# Mechanical.net
KiCad netlist of a schematic drawn in Altium Designer
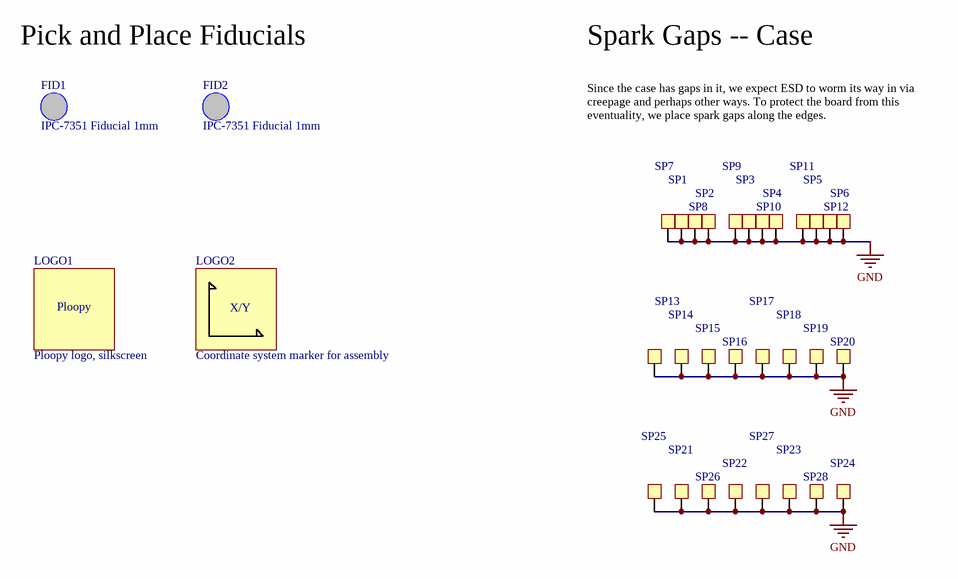
[diagram p0: Mechanical.SchDoc]

(export (version "E")
  (design (tool "Eeschema 10.0.6"))
  (components
    (comp (ref "FID1")
      (value "IPC-7351 Fiducial 1mm")
      (footprint "FIDUCIAL_1.5")
      (libsource (lib "Mechanical") (part "FIDUCIAL_1.5"))
    )
    (comp (ref "FID2")
      (value "IPC-7351 Fiducial 1mm")
      (footprint "FIDUCIAL_1.5")
      (libsource (lib "Mechanical") (part "FIDUCIAL_1.5"))
    )
    (comp (ref "LOGO1")
      (value "Ploopy logo, silkscreen")
      (footprint "PloopyLogo")
      (libsource (lib "Graphics") (part "PloopyLogo"))
    )
    (comp (ref "LOGO2")
      (value "Coordinate system marker for assembly")
      (footprint "Coordinate System")
      (libsource (lib "Graphics") (part "CoordinateSystem"))
    )
    (comp (ref "SP1")
      (value "Spark Gap")
      (footprint "SparkGap")
      (description "Open square pad for spark gapping")
      (libsource (lib "PCBFeatures") (part "Spark Gap"))
    )
    (comp (ref "SP2")
      (value "Spark Gap")
      (footprint "SparkGap")
      (description "Open square pad for spark gapping")
      (libsource (lib "PCBFeatures") (part "Spark Gap"))
    )
    (comp (ref "SP3")
      (value "Spark Gap")
      (footprint "SparkGap")
      (description "Open square pad for spark gapping")
      (libsource (lib "PCBFeatures") (part "Spark Gap"))
    )
    (comp (ref "SP4")
      (value "Spark Gap")
      (footprint "SparkGap")
      (description "Open square pad for spark gapping")
      (libsource (lib "PCBFeatures") (part "Spark Gap"))
    )
    (comp (ref "SP5")
      (value "Spark Gap")
      (footprint "SparkGap")
      (description "Open square pad for spark gapping")
      (libsource (lib "PCBFeatures") (part "Spark Gap"))
    )
    (comp (ref "SP6")
      (value "Spark Gap")
      (footprint "SparkGap")
      (description "Open square pad for spark gapping")
      (libsource (lib "PCBFeatures") (part "Spark Gap"))
    )
    (comp (ref "SP7")
      (value "Spark Gap")
      (footprint "SparkGap")
      (description "Open square pad for spark gapping")
      (libsource (lib "PCBFeatures") (part "Spark Gap"))
    )
    (comp (ref "SP8")
      (value "Spark Gap")
      (footprint "SparkGap")
      (description "Open square pad for spark gapping")
      (libsource (lib "PCBFeatures") (part "Spark Gap"))
    )
    (comp (ref "SP9")
      (value "Spark Gap")
      (footprint "SparkGap")
      (description "Open square pad for spark gapping")
      (libsource (lib "PCBFeatures") (part "Spark Gap"))
    )
    (comp (ref "SP10")
      (value "Spark Gap")
      (footprint "SparkGap")
      (description "Open square pad for spark gapping")
      (libsource (lib "PCBFeatures") (part "Spark Gap"))
    )
    (comp (ref "SP11")
      (value "Spark Gap")
      (footprint "SparkGap")
      (description "Open square pad for spark gapping")
      (libsource (lib "PCBFeatures") (part "Spark Gap"))
    )
    (comp (ref "SP12")
      (value "Spark Gap")
      (footprint "SparkGap")
      (description "Open square pad for spark gapping")
      (libsource (lib "PCBFeatures") (part "Spark Gap"))
    )
    (comp (ref "SP13")
      (value "Spark Gap")
      (footprint "SparkGap")
      (description "Open square pad for spark gapping")
      (libsource (lib "PCBFeatures") (part "Spark Gap"))
    )
    (comp (ref "SP14")
      (value "Spark Gap")
      (footprint "SparkGap")
      (description "Open square pad for spark gapping")
      (libsource (lib "PCBFeatures") (part "Spark Gap"))
    )
    (comp (ref "SP15")
      (value "Spark Gap")
      (footprint "SparkGap")
      (description "Open square pad for spark gapping")
      (libsource (lib "PCBFeatures") (part "Spark Gap"))
    )
    (comp (ref "SP16")
      (value "Spark Gap")
      (footprint "SparkGap")
      (description "Open square pad for spark gapping")
      (libsource (lib "PCBFeatures") (part "Spark Gap"))
    )
    (comp (ref "SP17")
      (value "Spark Gap")
      (footprint "SparkGap")
      (description "Open square pad for spark gapping")
      (libsource (lib "PCBFeatures") (part "Spark Gap"))
    )
    (comp (ref "SP18")
      (value "Spark Gap")
      (footprint "SparkGap")
      (description "Open square pad for spark gapping")
      (libsource (lib "PCBFeatures") (part "Spark Gap"))
    )
    (comp (ref "SP19")
      (value "Spark Gap")
      (footprint "SparkGap")
      (description "Open square pad for spark gapping")
      (libsource (lib "PCBFeatures") (part "Spark Gap"))
    )
    (comp (ref "SP20")
      (value "Spark Gap")
      (footprint "SparkGap")
      (description "Open square pad for spark gapping")
      (libsource (lib "PCBFeatures") (part "Spark Gap"))
    )
    (comp (ref "SP21")
      (value "Spark Gap")
      (footprint "SparkGap")
      (description "Open square pad for spark gapping")
      (libsource (lib "PCBFeatures") (part "Spark Gap"))
    )
    (comp (ref "SP22")
      (value "Spark Gap")
      (footprint "SparkGap")
      (description "Open square pad for spark gapping")
      (libsource (lib "PCBFeatures") (part "Spark Gap"))
    )
    (comp (ref "SP23")
      (value "Spark Gap")
      (footprint "SparkGap")
      (description "Open square pad for spark gapping")
      (libsource (lib "PCBFeatures") (part "Spark Gap"))
    )
    (comp (ref "SP24")
      (value "Spark Gap")
      (footprint "SparkGap")
      (description "Open square pad for spark gapping")
      (libsource (lib "PCBFeatures") (part "Spark Gap"))
    )
    (comp (ref "SP25")
      (value "Spark Gap")
      (footprint "SparkGap")
      (description "Open square pad for spark gapping")
      (libsource (lib "PCBFeatures") (part "Spark Gap"))
    )
    (comp (ref "SP26")
      (value "Spark Gap")
      (footprint "SparkGap")
      (description "Open square pad for spark gapping")
      (libsource (lib "PCBFeatures") (part "Spark Gap"))
    )
    (comp (ref "SP27")
      (value "Spark Gap")
      (footprint "SparkGap")
      (description "Open square pad for spark gapping")
      (libsource (lib "PCBFeatures") (part "Spark Gap"))
    )
    (comp (ref "SP28")
      (value "Spark Gap")
      (footprint "SparkGap")
      (description "Open square pad for spark gapping")
      (libsource (lib "PCBFeatures") (part "Spark Gap"))
    )
  )
  (nets
    (net (code "1") (name "GND") (class "Default")
      (node (ref "SP1") (pin "1") (pinfunction "1_1") (pintype "passive"))
      (node (ref "SP10") (pin "1") (pinfunction "1_1") (pintype "passive"))
      (node (ref "SP11") (pin "1") (pinfunction "1_1") (pintype "passive"))
      (node (ref "SP12") (pin "1") (pinfunction "1_1") (pintype "passive"))
      (node (ref "SP13") (pin "1") (pinfunction "1_1") (pintype "passive"))
      (node (ref "SP14") (pin "1") (pinfunction "1_1") (pintype "passive"))
      (node (ref "SP15") (pin "1") (pinfunction "1_1") (pintype "passive"))
      (node (ref "SP16") (pin "1") (pinfunction "1_1") (pintype "passive"))
      (node (ref "SP17") (pin "1") (pinfunction "1_1") (pintype "passive"))
      (node (ref "SP18") (pin "1") (pinfunction "1_1") (pintype "passive"))
      (node (ref "SP19") (pin "1") (pinfunction "1_1") (pintype "passive"))
      (node (ref "SP2") (pin "1") (pinfunction "1_1") (pintype "passive"))
      (node (ref "SP20") (pin "1") (pinfunction "1_1") (pintype "passive"))
      (node (ref "SP21") (pin "1") (pinfunction "1_1") (pintype "passive"))
      (node (ref "SP22") (pin "1") (pinfunction "1_1") (pintype "passive"))
      (node (ref "SP23") (pin "1") (pinfunction "1_1") (pintype "passive"))
      (node (ref "SP24") (pin "1") (pinfunction "1_1") (pintype "passive"))
      (node (ref "SP25") (pin "1") (pinfunction "1_1") (pintype "passive"))
      (node (ref "SP26") (pin "1") (pinfunction "1_1") (pintype "passive"))
      (node (ref "SP27") (pin "1") (pinfunction "1_1") (pintype "passive"))
      (node (ref "SP28") (pin "1") (pinfunction "1_1") (pintype "passive"))
      (node (ref "SP3") (pin "1") (pinfunction "1_1") (pintype "passive"))
      (node (ref "SP4") (pin "1") (pinfunction "1_1") (pintype "passive"))
      (node (ref "SP5") (pin "1") (pinfunction "1_1") (pintype "passive"))
      (node (ref "SP6") (pin "1") (pinfunction "1_1") (pintype "passive"))
      (node (ref "SP7") (pin "1") (pinfunction "1_1") (pintype "passive"))
      (node (ref "SP8") (pin "1") (pinfunction "1_1") (pintype "passive"))
      (node (ref "SP9") (pin "1") (pinfunction "1_1") (pintype "passive"))
    )
    (net (code "2") (name "unconnected-(FID1-Pad1)") (class "Default")
      (node (ref "FID1") (pin "1") (pinfunction "1_1") (pintype "passive"))
    )
    (net (code "3") (name "unconnected-(FID2-Pad1)") (class "Default")
      (node (ref "FID2") (pin "1") (pinfunction "1_1") (pintype "passive"))
    )
  )
)
